# RP2350A.net
KiCad netlist of a schematic drawn in Altium Designer
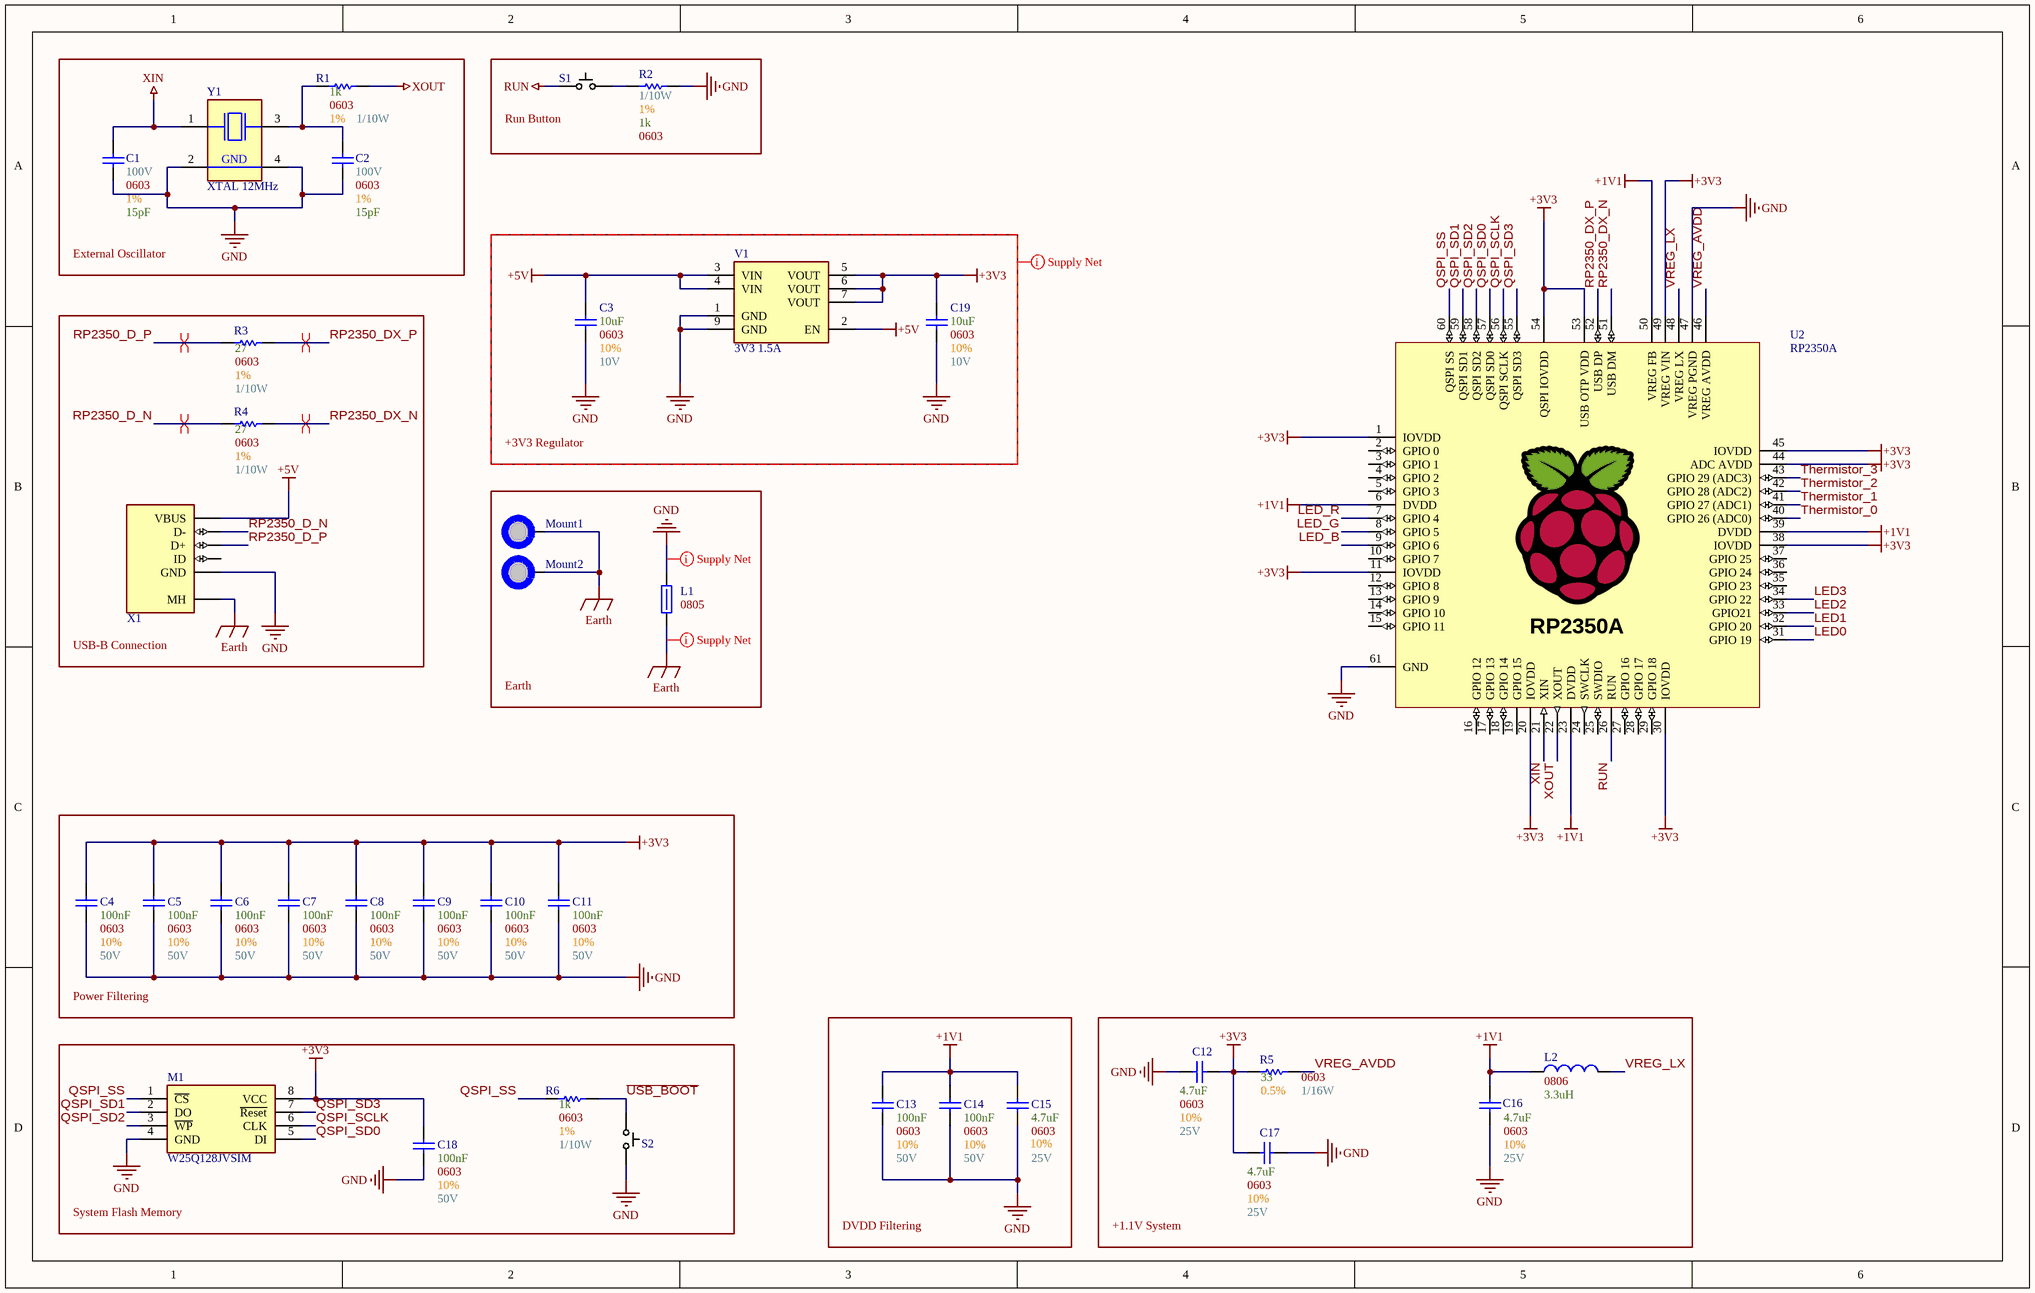
[diagram p0: RP2350A.SchDoc]

(export (version "E")
  (design (tool "Eeschema 10.0.6"))
  (components
    (comp (ref "C1")
      (value "[Cap] 0603 15pF 1% 100V")
      (footprint "[Cap] SMD 0603")
      (description "GCM1885C2A150FA16D")
      (fields
        (field (name "MAX VOLTAGE") "100V")
        (field (name "SIZE PACKAGE") "0603")
        (field (name "TOLERANCE") "1%")
        (field (name "CAPACITANCE") "15pF")
      )
      (libsource (lib "Capacitors") (part "[Cap] 0603 15pF 1% 100V"))
    )
    (comp (ref "C2")
      (value "[Cap] 0603 15pF 1% 100V")
      (footprint "[Cap] SMD 0603")
      (description "GCM1885C2A150FA16D")
      (fields
        (field (name "MAX VOLTAGE") "100V")
        (field (name "SIZE PACKAGE") "0603")
        (field (name "TOLERANCE") "1%")
        (field (name "CAPACITANCE") "15pF")
      )
      (libsource (lib "Capacitors") (part "[Cap] 0603 15pF 1% 100V"))
    )
    (comp (ref "C3")
      (value "[Cap] 0603 10uF 10% 10V")
      (footprint "[Cap] SMD 0603")
      (description "CL10A106KP8NNNC")
      (fields
        (field (name "MAX VOLTAGE") "10V")
        (field (name "SIZE PACKAGE") "0603")
        (field (name "TOLERANCE") "10%")
        (field (name "CAPACITANCE") "10uF")
      )
      (libsource (lib "Capacitors") (part "[Cap] 0603 10uF 10% 10V"))
    )
    (comp (ref "C4")
      (value "[Cap] 0603 0.1uF 10% 50V")
      (footprint "[Cap] SMD 0603")
      (description "CL10B104KB8NNNC")
      (fields
        (field (name "MAX VOLTAGE") "50V")
        (field (name "SIZE PACKAGE") "0603")
        (field (name "TOLERANCE") "10%")
        (field (name "CAPACITANCE") "100nF")
      )
      (libsource (lib "Capacitors") (part "[Cap] 0603 0.1uF 10% 50V"))
    )
    (comp (ref "C5")
      (value "[Cap] 0603 0.1uF 10% 50V")
      (footprint "[Cap] SMD 0603")
      (description "CL10B104KB8NNNC")
      (fields
        (field (name "MAX VOLTAGE") "50V")
        (field (name "SIZE PACKAGE") "0603")
        (field (name "TOLERANCE") "10%")
        (field (name "CAPACITANCE") "100nF")
      )
      (libsource (lib "Capacitors") (part "[Cap] 0603 0.1uF 10% 50V"))
    )
    (comp (ref "C6")
      (value "[Cap] 0603 0.1uF 10% 50V")
      (footprint "[Cap] SMD 0603")
      (description "CL10B104KB8NNNC")
      (fields
        (field (name "MAX VOLTAGE") "50V")
        (field (name "SIZE PACKAGE") "0603")
        (field (name "TOLERANCE") "10%")
        (field (name "CAPACITANCE") "100nF")
      )
      (libsource (lib "Capacitors") (part "[Cap] 0603 0.1uF 10% 50V"))
    )
    (comp (ref "C7")
      (value "[Cap] 0603 0.1uF 10% 50V")
      (footprint "[Cap] SMD 0603")
      (description "CL10B104KB8NNNC")
      (fields
        (field (name "MAX VOLTAGE") "50V")
        (field (name "SIZE PACKAGE") "0603")
        (field (name "TOLERANCE") "10%")
        (field (name "CAPACITANCE") "100nF")
      )
      (libsource (lib "Capacitors") (part "[Cap] 0603 0.1uF 10% 50V"))
    )
    (comp (ref "C8")
      (value "[Cap] 0603 0.1uF 10% 50V")
      (footprint "[Cap] SMD 0603")
      (description "CL10B104KB8NNNC")
      (fields
        (field (name "MAX VOLTAGE") "50V")
        (field (name "SIZE PACKAGE") "0603")
        (field (name "TOLERANCE") "10%")
        (field (name "CAPACITANCE") "100nF")
      )
      (libsource (lib "Capacitors") (part "[Cap] 0603 0.1uF 10% 50V"))
    )
    (comp (ref "C9")
      (value "[Cap] 0603 0.1uF 10% 50V")
      (footprint "[Cap] SMD 0603")
      (description "CL10B104KB8NNNC")
      (fields
        (field (name "MAX VOLTAGE") "50V")
        (field (name "SIZE PACKAGE") "0603")
        (field (name "TOLERANCE") "10%")
        (field (name "CAPACITANCE") "100nF")
      )
      (libsource (lib "Capacitors") (part "[Cap] 0603 0.1uF 10% 50V"))
    )
    (comp (ref "C10")
      (value "[Cap] 0603 0.1uF 10% 50V")
      (footprint "[Cap] SMD 0603")
      (description "CL10B104KB8NNNC")
      (fields
        (field (name "MAX VOLTAGE") "50V")
        (field (name "SIZE PACKAGE") "0603")
        (field (name "TOLERANCE") "10%")
        (field (name "CAPACITANCE") "100nF")
      )
      (libsource (lib "Capacitors") (part "[Cap] 0603 0.1uF 10% 50V"))
    )
    (comp (ref "C11")
      (value "[Cap] 0603 0.1uF 10% 50V")
      (footprint "[Cap] SMD 0603")
      (description "CL10B104KB8NNNC")
      (fields
        (field (name "MAX VOLTAGE") "50V")
        (field (name "SIZE PACKAGE") "0603")
        (field (name "TOLERANCE") "10%")
        (field (name "CAPACITANCE") "100nF")
      )
      (libsource (lib "Capacitors") (part "[Cap] 0603 0.1uF 10% 50V"))
    )
    (comp (ref "C12")
      (value "[Cap] 0603 4.7uF 10% 25V")
      (footprint "[Cap] SMD 0603")
      (description "GRM188R61E475KE11D")
      (fields
        (field (name "MAX VOLTAGE") "25V")
        (field (name "SIZE PACKAGE") "0603")
        (field (name "TOLERANCE") "10%")
        (field (name "CAPACITANCE") "4.7uF")
      )
      (libsource (lib "Capacitors") (part "[Cap] 0603 4.7uF 10% 25V"))
    )
    (comp (ref "C13")
      (value "[Cap] 0603 0.1uF 10% 50V")
      (footprint "[Cap] SMD 0603")
      (description "CL10B104KB8NNNC")
      (fields
        (field (name "MAX VOLTAGE") "50V")
        (field (name "SIZE PACKAGE") "0603")
        (field (name "TOLERANCE") "10%")
        (field (name "CAPACITANCE") "100nF")
      )
      (libsource (lib "Capacitors") (part "[Cap] 0603 0.1uF 10% 50V"))
    )
    (comp (ref "C14")
      (value "[Cap] 0603 0.1uF 10% 50V")
      (footprint "[Cap] SMD 0603")
      (description "CL10B104KB8NNNC")
      (fields
        (field (name "MAX VOLTAGE") "50V")
        (field (name "SIZE PACKAGE") "0603")
        (field (name "TOLERANCE") "10%")
        (field (name "CAPACITANCE") "100nF")
      )
      (libsource (lib "Capacitors") (part "[Cap] 0603 0.1uF 10% 50V"))
    )
    (comp (ref "C15")
      (value "[Cap] 0603 4.7uF 10% 25V")
      (footprint "[Cap] SMD 0603")
      (description "GRM188R61E475KE11D")
      (fields
        (field (name "MAX VOLTAGE") "25V")
        (field (name "SIZE PACKAGE") "0603")
        (field (name "TOLERANCE") "10%")
        (field (name "CAPACITANCE") "4.7uF")
      )
      (libsource (lib "Capacitors") (part "[Cap] 0603 4.7uF 10% 25V"))
    )
    (comp (ref "C16")
      (value "[Cap] 0603 4.7uF 10% 25V")
      (footprint "[Cap] SMD 0603")
      (description "GRM188R61E475KE11D")
      (fields
        (field (name "MAX VOLTAGE") "25V")
        (field (name "SIZE PACKAGE") "0603")
        (field (name "TOLERANCE") "10%")
        (field (name "CAPACITANCE") "4.7uF")
      )
      (libsource (lib "Capacitors") (part "[Cap] 0603 4.7uF 10% 25V"))
    )
    (comp (ref "C17")
      (value "[Cap] 0603 4.7uF 10% 25V")
      (footprint "[Cap] SMD 0603")
      (description "GRM188R61E475KE11D")
      (fields
        (field (name "MAX VOLTAGE") "25V")
        (field (name "SIZE PACKAGE") "0603")
        (field (name "TOLERANCE") "10%")
        (field (name "CAPACITANCE") "4.7uF")
      )
      (libsource (lib "Capacitors") (part "[Cap] 0603 4.7uF 10% 25V"))
    )
    (comp (ref "C18")
      (value "[Cap] 0603 0.1uF 10% 50V")
      (footprint "[Cap] SMD 0603")
      (description "CL10B104KB8NNNC")
      (fields
        (field (name "MAX VOLTAGE") "50V")
        (field (name "SIZE PACKAGE") "0603")
        (field (name "TOLERANCE") "10%")
        (field (name "CAPACITANCE") "100nF")
      )
      (libsource (lib "Capacitors") (part "[Cap] 0603 0.1uF 10% 50V"))
    )
    (comp (ref "C19")
      (value "[Cap] 0603 10uF 10% 10V")
      (footprint "[Cap] SMD 0603")
      (description "CL10A106KP8NNNC")
      (fields
        (field (name "MAX VOLTAGE") "10V")
        (field (name "SIZE PACKAGE") "0603")
        (field (name "TOLERANCE") "10%")
        (field (name "CAPACITANCE") "10uF")
      )
      (libsource (lib "Capacitors") (part "[Cap] 0603 10uF 10% 10V"))
    )
    (comp (ref "L1")
      (value "652-MH2029-300Y")
      (footprint "[Ferrite] SMD 0805")
      (fields (field (name "SIZE PACKAGE") "0805"))
      (libsource (lib "Ferrite Beads") (part "[Ferrite] SMD 0805 3A 30ohm"))
    )
    (comp (ref "L2")
      (value "[3.3uH] SMD 0806 2.1A")
      (footprint "[Inductor] SMD 0806")
      (description "AOTA-B201610S3R3-101-T")
      (fields (field (name "PACKAGE") "0806") (field (name "INDUCTANCE") "3.3uH"))
      (libsource (lib "Inductors") (part "[3.3uH] SMD 0806 2.1A"))
    )
    (comp (ref "M1")
      (value "W25Q128JVSIM")
      (footprint "[Flash] 128MBit")
      (libsource (lib "Memory") (part "[Flash] 128MBit"))
    )
    (comp (ref "Mount1")
      (value "M3 Mount Hole")
      (footprint "[Mount] M3 Mount Hole")
      (description "Place at least 4.5mm from board edge. Plated.")
      (libsource (lib "Mounts, Pads, Vias") (part "[Mount] M3 Mount Hole"))
    )
    (comp (ref "Mount2")
      (value "M3 Mount Hole")
      (footprint "[Mount] M3 Mount Hole")
      (description "Place at least 4.5mm from board edge. Plated.")
      (libsource (lib "Mounts, Pads, Vias") (part "[Mount] M3 Mount Hole"))
    )
    (comp (ref "R1")
      (value "[1k] SMD 0603 1% 1/10W")
      (footprint "[Res] SMD 0603")
      (description "RMCF0603FT1K00")
      (fields
        (field (name "WATTAGE") "1/10W")
        (field (name "TOLERANCE") "1%")
        (field (name "RESISTANCE") "1k")
        (field (name "SIZE PACKAGE") "0603")
      )
      (libsource (lib "Resistors") (part "[1k] SMD 0603 1% 1/10W"))
    )
    (comp (ref "R2")
      (value "[1k] SMD 0603 1% 1/10W")
      (footprint "[Res] SMD 0603")
      (description "RMCF0603FT1K00")
      (fields
        (field (name "WATTAGE") "1/10W")
        (field (name "TOLERANCE") "1%")
        (field (name "RESISTANCE") "1k")
        (field (name "SIZE PACKAGE") "0603")
      )
      (libsource (lib "Resistors") (part "[1k] SMD 0603 1% 1/10W"))
    )
    (comp (ref "R3")
      (value "[27] SMD 0603 1% 1/10W")
      (footprint "[Res] SMD 0603")
      (description "MCT06030C2709FP500")
      (fields
        (field (name "WATTAGE") "1/10W")
        (field (name "TOLERANCE") "1%")
        (field (name "RESISTANCE") "27")
        (field (name "SIZE PACKAGE") "0603")
      )
      (libsource (lib "Resistors") (part "[27] SMD 0603 1% 1/10W"))
    )
    (comp (ref "R4")
      (value "[27] SMD 0603 1% 1/10W")
      (footprint "[Res] SMD 0603")
      (description "MCT06030C2709FP500")
      (fields
        (field (name "WATTAGE") "1/10W")
        (field (name "TOLERANCE") "1%")
        (field (name "RESISTANCE") "27")
        (field (name "SIZE PACKAGE") "0603")
      )
      (libsource (lib "Resistors") (part "[27] SMD 0603 1% 1/10W"))
    )
    (comp (ref "R5")
      (value "[33] SMD 0603 0.5% 1/16W")
      (footprint "[Res] SMD 0603")
      (description "RR0816Q-330-D")
      (fields
        (field (name "WATTAGE") "1/16W")
        (field (name "TOLERANCE") "0.5%")
        (field (name "RESISTANCE") "33")
        (field (name "SIZE PACKAGE") "0603")
      )
      (libsource (lib "Resistors") (part "[33] SMD 0603 0.5% 1/16W"))
    )
    (comp (ref "R6")
      (value "[1k] SMD 0603 1% 1/10W")
      (footprint "[Res] SMD 0603")
      (description "RMCF0603FT1K00")
      (fields
        (field (name "WATTAGE") "1/10W")
        (field (name "TOLERANCE") "1%")
        (field (name "RESISTANCE") "1k")
        (field (name "SIZE PACKAGE") "0603")
      )
      (libsource (lib "Resistors") (part "[1k] SMD 0603 1% 1/10W"))
    )
    (comp (ref "S1")
      (value "[SPST] SMD Pushbutton")
      (footprint "[SPST] SMD Pushbutton")
      (description "PTS815SJM250SMTRLFS")
      (libsource (lib "Switches") (part "[SPST] SMD Pushbutton"))
    )
    (comp (ref "S2")
      (value "[SPST] SMD Pushbutton")
      (footprint "[SPST] SMD Pushbutton")
      (description "PTS815SJM250SMTRLFS")
      (libsource (lib "Switches") (part "[SPST] SMD Pushbutton"))
    )
    (comp (ref "U2")
      (value "RP2350A")
      (footprint "[MCU] RP2350A")
      (description "QFN-60 Package")
      (libsource (lib "MCUs") (part "[MCU] RP2350A"))
    )
    (comp (ref "V1")
      (value "3V3 1.5A")
      (footprint "[Linear] 3V3 1.5A")
      (description "AP7362A-33SP-13")
      (libsource (lib "Voltage Regulators") (part "[Linear] SMD 3V3 1.5A"))
    )
    (comp (ref "X1")
      (value "[USB] Type-B Mini")
      (footprint "[USB] Type-B Mini")
      (description "MUSB-05-S-B-SM-A-K-TR")
      (libsource (lib "Connectors") (part "[USB] Type-B Mini"))
    )
    (comp (ref "Y1")
      (value "XTAL 12MHz")
      (footprint "[Crystal] SMD 12MHz")
      (description "815-ABM8-272-T3")
      (libsource (lib "Crystals and Oscillators") (part "[Crystal] SMD 12MHz"))
    )
  )
  (nets
    (net (code "1") (name "+1V1") (class "Default")
      (node (ref "C13") (pin "2") (pinfunction "2_2") (pintype "passive"))
      (node (ref "C14") (pin "2") (pinfunction "2_2") (pintype "passive"))
      (node (ref "C15") (pin "2") (pinfunction "2_2") (pintype "passive"))
      (node (ref "C16") (pin "1") (pinfunction "1_1") (pintype "passive"))
      (node (ref "L2") (pin "1") (pinfunction "1_1") (pintype "passive"))
      (node (ref "U2") (pin "23") (pinfunction "DVDD_23") (pintype "power_in"))
      (node (ref "U2") (pin "39") (pinfunction "DVDD_39") (pintype "power_in"))
      (node (ref "U2") (pin "50") (pinfunction "VREG_FB_50") (pintype "power_in"))
      (node (ref "U2") (pin "6") (pinfunction "DVDD_6") (pintype "power_in"))
    )
    (net (code "2") (name "+3V3") (class "Default")
      (node (ref "C10") (pin "2") (pinfunction "2_2") (pintype "passive"))
      (node (ref "C11") (pin "2") (pinfunction "2_2") (pintype "passive"))
      (node (ref "C12") (pin "1") (pinfunction "1_1") (pintype "passive"))
      (node (ref "C17") (pin "2") (pinfunction "2_2") (pintype "passive"))
      (node (ref "C18") (pin "2") (pinfunction "2_2") (pintype "passive"))
      (node (ref "C19") (pin "2") (pinfunction "2_2") (pintype "passive"))
      (node (ref "C4") (pin "2") (pinfunction "2_2") (pintype "passive"))
      (node (ref "C5") (pin "2") (pinfunction "2_2") (pintype "passive"))
      (node (ref "C6") (pin "2") (pinfunction "2_2") (pintype "passive"))
      (node (ref "C7") (pin "2") (pinfunction "2_2") (pintype "passive"))
      (node (ref "C8") (pin "2") (pinfunction "2_2") (pintype "passive"))
      (node (ref "C9") (pin "2") (pinfunction "2_2") (pintype "passive"))
      (node (ref "M1") (pin "8") (pinfunction "VCC_8") (pintype "passive"))
      (node (ref "R5") (pin "1") (pinfunction "1_1") (pintype "passive"))
      (node (ref "U2") (pin "1") (pinfunction "IOVDD_1") (pintype "power_in"))
      (node (ref "U2") (pin "11") (pinfunction "IOVDD_11") (pintype "power_in"))
      (node (ref "U2") (pin "20") (pinfunction "IOVDD_20") (pintype "power_in"))
      (node (ref "U2") (pin "30") (pinfunction "IOVDD_30") (pintype "power_in"))
      (node (ref "U2") (pin "38") (pinfunction "IOVDD_38") (pintype "power_in"))
      (node (ref "U2") (pin "44") (pinfunction "ADC_AVDD_44") (pintype "power_in"))
      (node (ref "U2") (pin "45") (pinfunction "IOVDD_45") (pintype "power_in"))
      (node (ref "U2") (pin "49") (pinfunction "VREG_VIN_49") (pintype "power_in"))
      (node (ref "U2") (pin "53") (pinfunction "USB_OTP_VDD_53") (pintype "power_in"))
      (node (ref "U2") (pin "54") (pinfunction "QSPI_IOVDD_54") (pintype "power_in"))
      (node (ref "V1") (pin "5") (pinfunction "VOUT_5") (pintype "passive"))
      (node (ref "V1") (pin "6") (pinfunction "VOUT_6") (pintype "passive"))
      (node (ref "V1") (pin "7") (pinfunction "VOUT_7") (pintype "passive"))
    )
    (net (code "3") (name "+5V") (class "Default")
      (node (ref "C3") (pin "2") (pinfunction "2_2") (pintype "passive"))
      (node (ref "V1") (pin "2") (pinfunction "EN_2") (pintype "passive"))
      (node (ref "V1") (pin "3") (pinfunction "VIN_3") (pintype "passive"))
      (node (ref "V1") (pin "4") (pinfunction "VIN_4") (pintype "passive"))
      (node (ref "X1") (pin "1") (pinfunction "VBUS_1") (pintype "power_in"))
    )
    (net (code "4") (name "/LED0") (class "Default")
      (node (ref "U2") (pin "31") (pinfunction "GPIO_19_31") (pintype "bidirectional"))
    )
    (net (code "5") (name "/LED1") (class "Default")
      (node (ref "U2") (pin "32") (pinfunction "GPIO_20_32") (pintype "bidirectional"))
    )
    (net (code "6") (name "/LED2") (class "Default")
      (node (ref "U2") (pin "33") (pinfunction "GPIO21_33") (pintype "bidirectional"))
    )
    (net (code "7") (name "/LED3") (class "Default")
      (node (ref "U2") (pin "34") (pinfunction "GPIO_22_34") (pintype "bidirectional"))
    )
    (net (code "8") (name "/LED_B") (class "Default")
      (node (ref "U2") (pin "9") (pinfunction "GPIO_6_9") (pintype "bidirectional"))
    )
    (net (code "9") (name "/LED_G") (class "Default")
      (node (ref "U2") (pin "8") (pinfunction "GPIO_5_8") (pintype "bidirectional"))
    )
    (net (code "10") (name "/LED_R") (class "Default")
      (node (ref "U2") (pin "7") (pinfunction "GPIO_4_7") (pintype "bidirectional"))
    )
    (net (code "11") (name "/QSPI_SCLK") (class "Default")
      (node (ref "M1") (pin "6") (pinfunction "CLK_6") (pintype "passive"))
      (node (ref "U2") (pin "56") (pinfunction "QSPI_SCLK_56") (pintype "bidirectional"))
    )
    (net (code "12") (name "/QSPI_SD0") (class "Default")
      (node (ref "M1") (pin "5") (pinfunction "DI_5") (pintype "passive"))
      (node (ref "U2") (pin "57") (pinfunction "QSPI_SD0_57") (pintype "bidirectional"))
    )
    (net (code "13") (name "/QSPI_SD1") (class "Default")
      (node (ref "M1") (pin "2") (pinfunction "DO_2") (pintype "passive"))
      (node (ref "U2") (pin "59") (pinfunction "QSPI_SD1_59") (pintype "bidirectional"))
    )
    (net (code "14") (name "/QSPI_SD2") (class "Default")
      (node (ref "M1") (pin "3") (pinfunction "~{WP}_3") (pintype "passive"))
      (node (ref "U2") (pin "58") (pinfunction "QSPI_SD2_58") (pintype "bidirectional"))
    )
    (net (code "15") (name "/QSPI_SD3") (class "Default")
      (node (ref "M1") (pin "7") (pinfunction "~{Reset}_7") (pintype "passive"))
      (node (ref "U2") (pin "55") (pinfunction "QSPI_SD3_55") (pintype "bidirectional"))
    )
    (net (code "16") (name "/QSPI_SS") (class "Default")
      (node (ref "M1") (pin "1") (pinfunction "~{CS}_1") (pintype "passive"))
      (node (ref "R6") (pin "1") (pinfunction "1_1") (pintype "passive"))
      (node (ref "U2") (pin "60") (pinfunction "QSPI_SS_60") (pintype "bidirectional"))
    )
    (net (code "17") (name "/RP2350_DX_N") (class "Default")
      (node (ref "R4") (pin "2") (pinfunction "2_2") (pintype "passive"))
      (node (ref "U2") (pin "51") (pinfunction "USB_DM_51") (pintype "bidirectional"))
    )
    (net (code "18") (name "/RP2350_DX_P") (class "Default")
      (node (ref "R3") (pin "2") (pinfunction "2_2") (pintype "passive"))
      (node (ref "U2") (pin "52") (pinfunction "USB_DP_52") (pintype "bidirectional"))
    )
    (net (code "19") (name "/RP2350_D_N") (class "Default")
      (node (ref "R4") (pin "1") (pinfunction "1_1") (pintype "passive"))
      (node (ref "X1") (pin "2") (pinfunction "D-_2") (pintype "bidirectional"))
    )
    (net (code "20") (name "/RP2350_D_P") (class "Default")
      (node (ref "R3") (pin "1") (pinfunction "1_1") (pintype "passive"))
      (node (ref "X1") (pin "3") (pinfunction "D+_3") (pintype "bidirectional"))
    )
    (net (code "21") (name "/Thermistor_0") (class "Default")
      (node (ref "U2") (pin "40") (pinfunction "GPIO_26_(ADC0)_40") (pintype "bidirectional"))
    )
    (net (code "22") (name "/Thermistor_1") (class "Default")
      (node (ref "U2") (pin "41") (pinfunction "GPIO_27_(ADC1)_41") (pintype "bidirectional"))
    )
    (net (code "23") (name "/Thermistor_2") (class "Default")
      (node (ref "U2") (pin "42") (pinfunction "GPIO_28_(ADC2)_42") (pintype "bidirectional"))
    )
    (net (code "24") (name "/Thermistor_3") (class "Default")
      (node (ref "U2") (pin "43") (pinfunction "GPIO_29_(ADC3)_43") (pintype "bidirectional"))
    )
    (net (code "25") (name "/VREG_AVDD") (class "Default")
      (node (ref "R5") (pin "2") (pinfunction "2_2") (pintype "passive"))
      (node (ref "U2") (pin "46") (pinfunction "VREG_AVDD_46") (pintype "power_in"))
    )
    (net (code "26") (name "/VREG_LX") (class "Default")
      (node (ref "L2") (pin "2") (pinfunction "2_2") (pintype "passive"))
      (node (ref "U2") (pin "48") (pinfunction "VREG_LX_48") (pintype "power_in"))
    )
    (net (code "27") (name "/~{USB_BOOT}") (class "Default")
      (node (ref "R6") (pin "2") (pinfunction "2_2") (pintype "passive"))
      (node (ref "S2") (pin "1") (pintype "power_in"))
    )
    (net (code "28") (name "Earth") (class "Default")
      (node (ref "L1") (pin "1") (pinfunction "1_1") (pintype "passive"))
      (node (ref "Mount1") (pin "1") (pintype "power_in"))
      (node (ref "Mount2") (pin "1") (pintype "power_in"))
      (node (ref "X1") (pin "MH") (pinfunction "MH_MH") (pintype "power_in"))
    )
    (net (code "29") (name "GND") (class "Default")
      (node (ref "C1") (pin "1") (pinfunction "1_1") (pintype "passive"))
      (node (ref "C10") (pin "1") (pinfunction "1_1") (pintype "passive"))
      (node (ref "C11") (pin "1") (pinfunction "1_1") (pintype "passive"))
      (node (ref "C12") (pin "2") (pinfunction "2_2") (pintype "passive"))
      (node (ref "C13") (pin "1") (pinfunction "1_1") (pintype "passive"))
      (node (ref "C14") (pin "1") (pinfunction "1_1") (pintype "passive"))
      (node (ref "C15") (pin "1") (pinfunction "1_1") (pintype "passive"))
      (node (ref "C16") (pin "2") (pinfunction "2_2") (pintype "passive"))
      (node (ref "C17") (pin "1") (pinfunction "1_1") (pintype "passive"))
      (node (ref "C18") (pin "1") (pinfunction "1_1") (pintype "passive"))
      (node (ref "C19") (pin "1") (pinfunction "1_1") (pintype "passive"))
      (node (ref "C2") (pin "1") (pinfunction "1_1") (pintype "passive"))
      (node (ref "C3") (pin "1") (pinfunction "1_1") (pintype "passive"))
      (node (ref "C4") (pin "1") (pinfunction "1_1") (pintype "passive"))
      (node (ref "C5") (pin "1") (pinfunction "1_1") (pintype "passive"))
      (node (ref "C6") (pin "1") (pinfunction "1_1") (pintype "passive"))
      (node (ref "C7") (pin "1") (pinfunction "1_1") (pintype "passive"))
      (node (ref "C8") (pin "1") (pinfunction "1_1") (pintype "passive"))
      (node (ref "C9") (pin "1") (pinfunction "1_1") (pintype "passive"))
      (node (ref "L1") (pin "2") (pinfunction "2_2") (pintype "passive"))
      (node (ref "M1") (pin "4") (pinfunction "GND_4") (pintype "passive"))
      (node (ref "R2") (pin "1") (pinfunction "1_1") (pintype "passive"))
      (node (ref "S2") (pin "2") (pintype "power_in"))
      (node (ref "U2") (pin "47") (pinfunction "VREG_PGND_47") (pintype "power_in"))
      (node (ref "U2") (pin "61") (pinfunction "GND_61") (pintype "power_in"))
      (node (ref "V1") (pin "1") (pinfunction "GND_1") (pintype "passive"))
      (node (ref "V1") (pin "9") (pinfunction "GND_9") (pintype "passive"))
      (node (ref "X1") (pin "5") (pinfunction "GND_5") (pintype "power_in"))
      (node (ref "Y1") (pin "2") (pinfunction "GND_2") (pintype "power_in"))
      (node (ref "Y1") (pin "4") (pinfunction "GND_4") (pintype "power_in"))
    )
    (net (code "30") (name "Net-(R2-Pad2)") (class "Default")
      (node (ref "R2") (pin "2") (pinfunction "2_2") (pintype "passive"))
      (node (ref "S1") (pin "2") (pintype "power_in"))
    )
    (net (code "31") (name "Net-(Y1-XTAL2)") (class "Default")
      (node (ref "C2") (pin "2") (pinfunction "2_2") (pintype "passive"))
      (node (ref "R1") (pin "1") (pinfunction "1_1") (pintype "passive"))
      (node (ref "Y1") (pin "3") (pinfunction "XTAL2_3") (pintype "power_in"))
    )
    (net (code "32") (name "RUN") (class "Default")
      (node (ref "S1") (pin "1") (pintype "power_in"))
      (node (ref "U2") (pin "26") (pinfunction "RUN_26") (pintype "passive"))
    )
    (net (code "33") (name "XIN") (class "Default")
      (node (ref "C1") (pin "2") (pinfunction "2_2") (pintype "passive"))
      (node (ref "U2") (pin "21") (pinfunction "XIN_21") (pintype "input"))
      (node (ref "Y1") (pin "1") (pinfunction "XTAL1_1") (pintype "power_in"))
    )
    (net (code "34") (name "XOUT") (class "Default")
      (node (ref "R1") (pin "2") (pinfunction "2_2") (pintype "passive"))
      (node (ref "U2") (pin "22") (pinfunction "XOUT_22") (pintype "output"))
    )
    (net (code "35") (name "unconnected-(U2-GPIO_0-Pad2)") (class "Default")
      (node (ref "U2") (pin "2") (pinfunction "GPIO_0_2") (pintype "bidirectional"))
    )
    (net (code "36") (name "unconnected-(U2-GPIO_1-Pad3)") (class "Default")
      (node (ref "U2") (pin "3") (pinfunction "GPIO_1_3") (pintype "bidirectional"))
    )
    (net (code "37") (name "unconnected-(U2-GPIO_2-Pad4)") (class "Default")
      (node (ref "U2") (pin "4") (pinfunction "GPIO_2_4") (pintype "bidirectional"))
    )
    (net (code "38") (name "unconnected-(U2-GPIO_3-Pad5)") (class "Default")
      (node (ref "U2") (pin "5") (pinfunction "GPIO_3_5") (pintype "bidirectional"))
    )
    (net (code "39") (name "unconnected-(U2-GPIO_7-Pad10)") (class "Default")
      (node (ref "U2") (pin "10") (pinfunction "GPIO_7_10") (pintype "bidirectional"))
    )
    (net (code "40") (name "unconnected-(U2-GPIO_8-Pad12)") (class "Default")
      (node (ref "U2") (pin "12") (pinfunction "GPIO_8_12") (pintype "bidirectional"))
    )
    (net (code "41") (name "unconnected-(U2-GPIO_9-Pad13)") (class "Default")
      (node (ref "U2") (pin "13") (pinfunction "GPIO_9_13") (pintype "bidirectional"))
    )
    (net (code "42") (name "unconnected-(U2-GPIO_10-Pad14)") (class "Default")
      (node (ref "U2") (pin "14") (pinfunction "GPIO_10_14") (pintype "bidirectional"))
    )
    (net (code "43") (name "unconnected-(U2-GPIO_11-Pad15)") (class "Default")
      (node (ref "U2") (pin "15") (pinfunction "GPIO_11_15") (pintype "bidirectional"))
    )
    (net (code "44") (name "unconnected-(U2-GPIO_12-Pad16)") (class "Default")
      (node (ref "U2") (pin "16") (pinfunction "GPIO_12_16") (pintype "bidirectional"))
    )
    (net (code "45") (name "unconnected-(U2-GPIO_13-Pad17)") (class "Default")
      (node (ref "U2") (pin "17") (pinfunction "GPIO_13_17") (pintype "bidirectional"))
    )
    (net (code "46") (name "unconnected-(U2-GPIO_14-Pad18)") (class "Default")
      (node (ref "U2") (pin "18") (pinfunction "GPIO_14_18") (pintype "bidirectional"))
    )
    (net (code "47") (name "unconnected-(U2-GPIO_15-Pad19)") (class "Default")
      (node (ref "U2") (pin "19") (pinfunction "GPIO_15_19") (pintype "power_in"))
    )
    (net (code "48") (name "unconnected-(U2-GPIO_16-Pad27)") (class "Default")
      (node (ref "U2") (pin "27") (pinfunction "GPIO_16_27") (pintype "bidirectional"))
    )
    (net (code "49") (name "unconnected-(U2-GPIO_17-Pad28)") (class "Default")
      (node (ref "U2") (pin "28") (pinfunction "GPIO_17_28") (pintype "bidirectional"))
    )
    (net (code "50") (name "unconnected-(U2-GPIO_18-Pad29)") (class "Default")
      (node (ref "U2") (pin "29") (pinfunction "GPIO_18_29") (pintype "bidirectional"))
    )
    (net (code "51") (name "unconnected-(U2-GPIO_23-Pad35)") (class "Default")
      (node (ref "U2") (pin "35") (pinfunction "GPIO_23_35") (pintype "bidirectional"))
    )
    (net (code "52") (name "unconnected-(U2-GPIO_24-Pad36)") (class "Default")
      (node (ref "U2") (pin "36") (pinfunction "GPIO_24_36") (pintype "bidirectional"))
    )
    (net (code "53") (name "unconnected-(U2-GPIO_25-Pad37)") (class "Default")
      (node (ref "U2") (pin "37") (pinfunction "GPIO_25_37") (pintype "bidirectional"))
    )
    (net (code "54") (name "unconnected-(U2-SWCLK-Pad24)") (class "Default")
      (node (ref "U2") (pin "24") (pinfunction "SWCLK_24") (pintype "output"))
    )
    (net (code "55") (name "unconnected-(U2-SWDIO-Pad25)") (class "Default")
      (node (ref "U2") (pin "25") (pinfunction "SWDIO_25") (pintype "bidirectional"))
    )
    (net (code "56") (name "unconnected-(X1-ID-Pad4)") (class "Default")
      (node (ref "X1") (pin "4") (pinfunction "ID_4") (pintype "bidirectional"))
    )
  )
)
